# Sheet1.net
KiCad netlist of a schematic drawn in Altium Designer
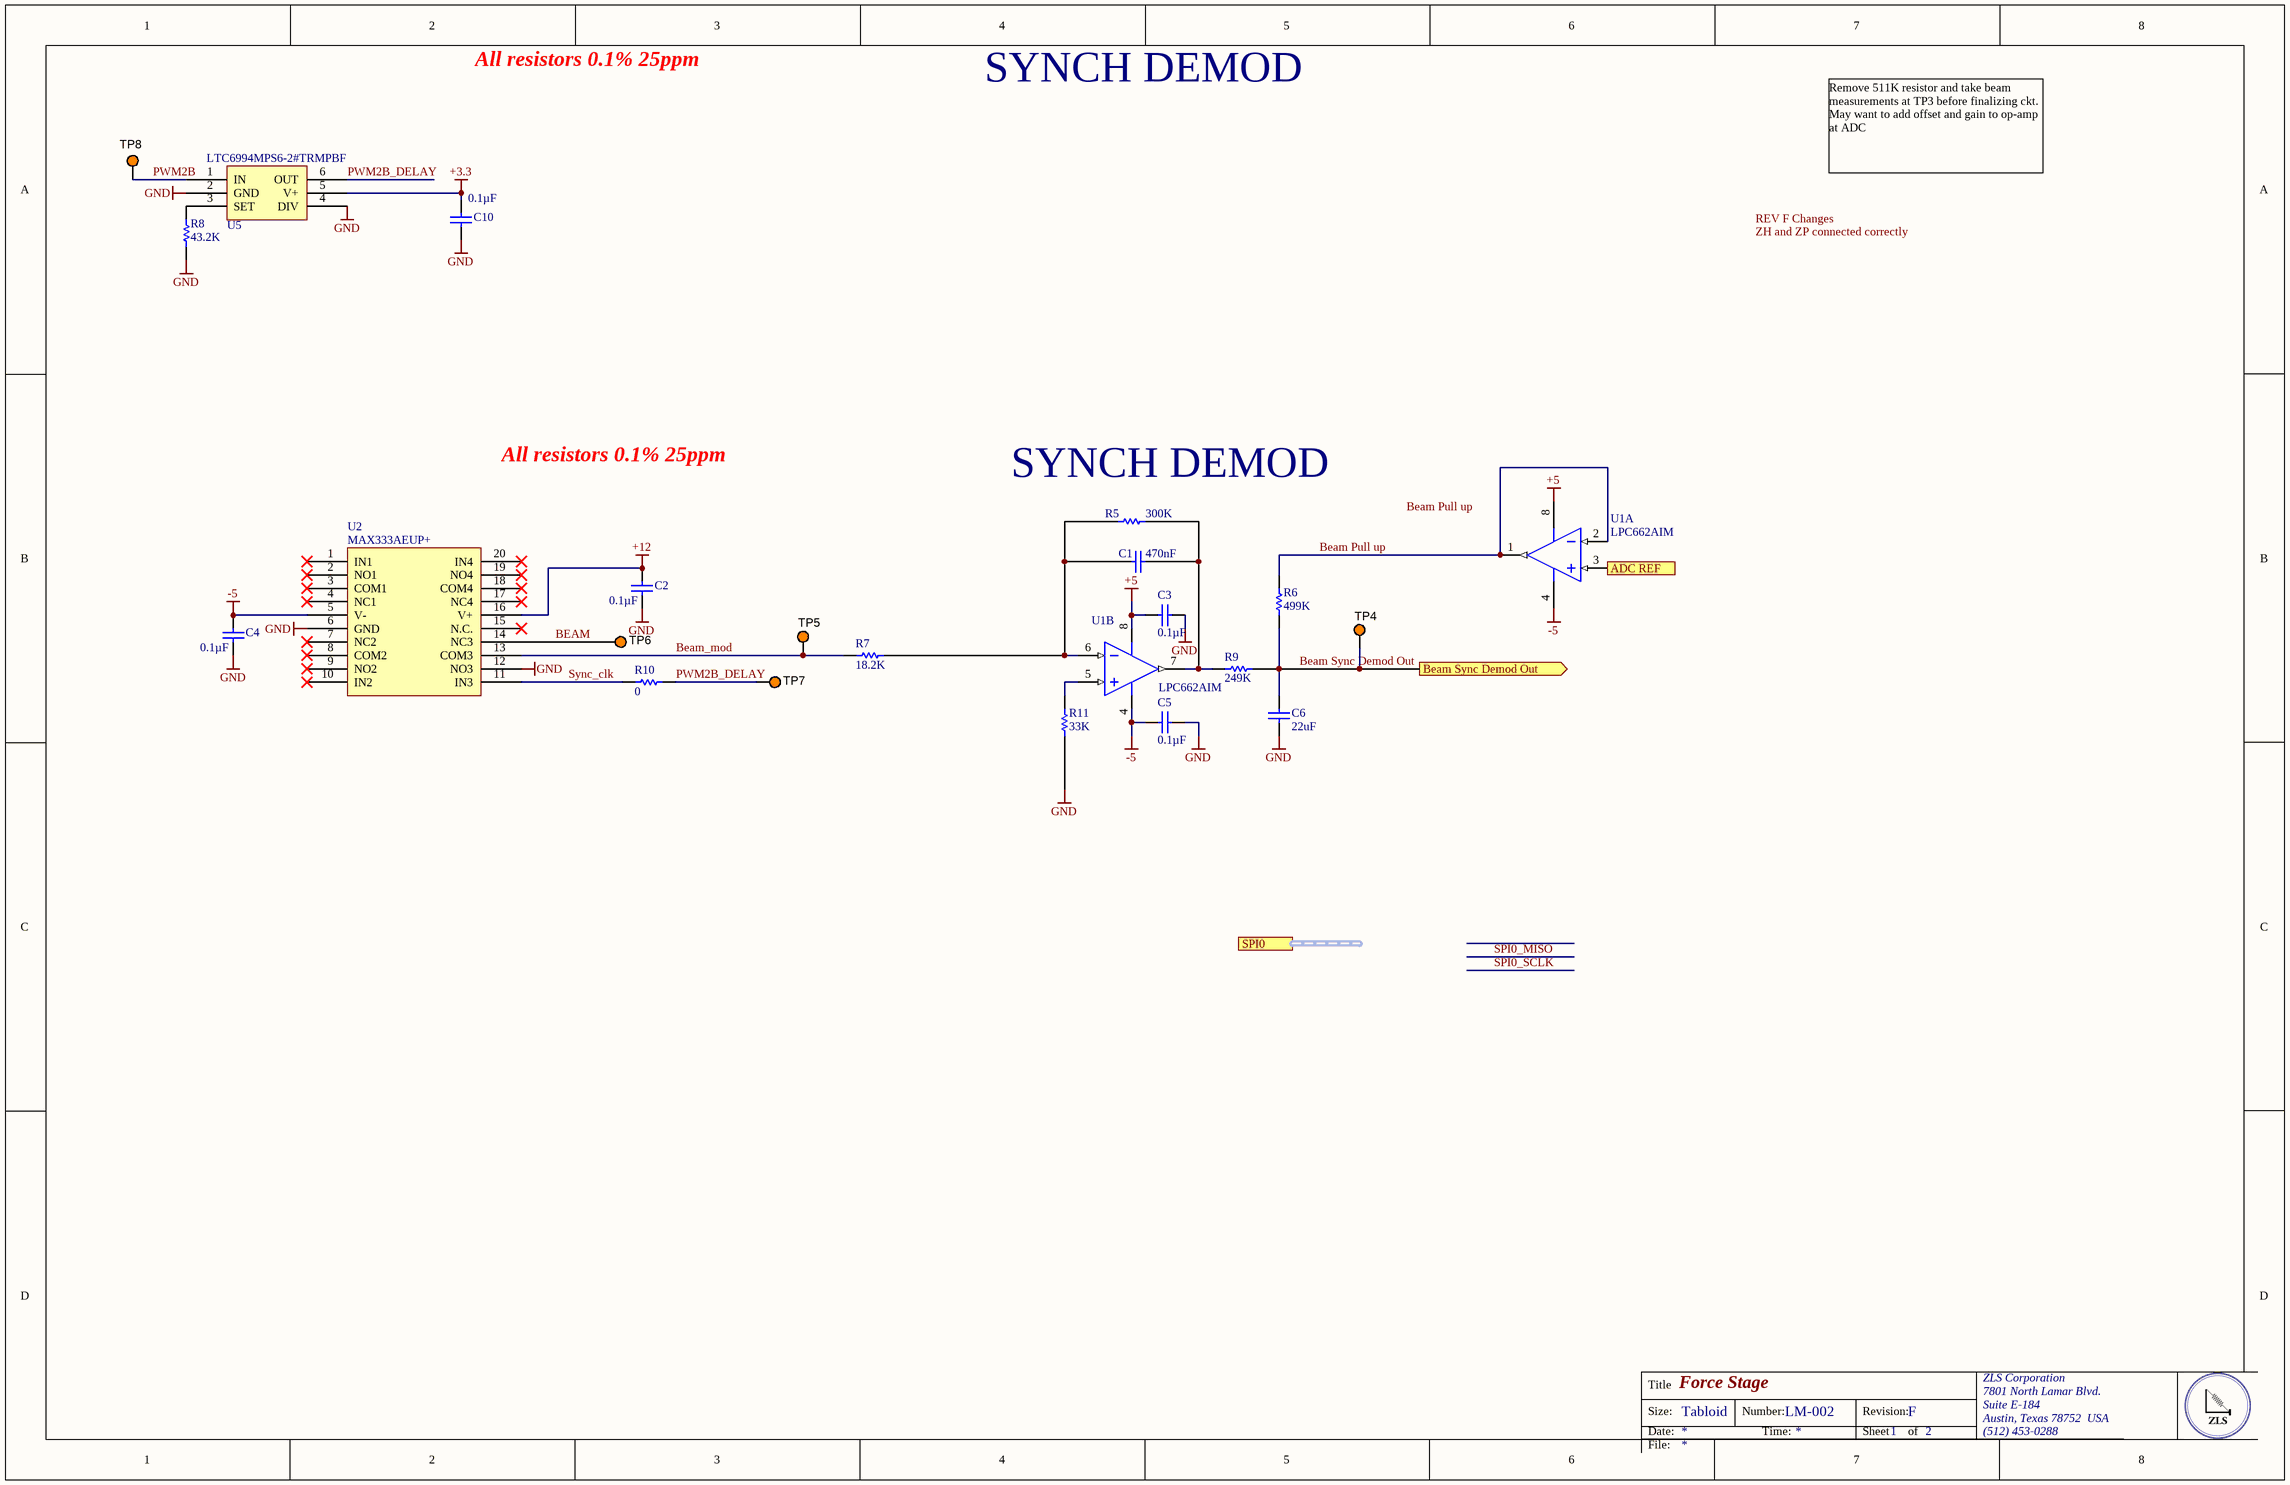
[diagram p0: Sheet1.SchDoc]

(export (version "E")
  (design (tool "Eeschema 10.0.6"))
  (components
    (comp (ref "C1")
      (value "470nF")
      (footprint "CAPC0805(2012)75_L")
      (description "CAP CER 0.47UF 25V X7R 0805")
      (fields
        (field (name "MANUFACTURER") "Murata Electronics North America")
        (field (name "MANUFACTURER PART NUMBER") "GRM219R71E474KA88D")
      )
      (libsource (lib "Altium Content Vault") (part "CMP-1036-02117-1"))
    )
    (comp (ref "C2")
      (value "CAP CER 0.1UF 25V X7R 0805")
      (footprint "CAPC0805(2012)145_N")
      (fields
        (field (name "MANUFACTURER") "Murata Electronics North America")
        (field (name "MANUFACTURER PART NUMBER") "GRM21BR71E104KA01L")
        (field (name "CAPACITANCE") "0.1µF")
        (field (name "TOLERANCE") "±10%")
      )
      (libsource (lib "Altium Content Vault") (part "CMP-1036-04795-1"))
    )
    (comp (ref "C3")
      (value "CAP CER 0.1UF 25V X7R 0805")
      (footprint "CAPC0805(2012)145_N")
      (fields
        (field (name "MANUFACTURER") "Murata Electronics North America")
        (field (name "MANUFACTURER PART NUMBER") "GRM21BR71E104KA01L")
        (field (name "CAPACITANCE") "0.1µF")
        (field (name "TOLERANCE") "±10%")
      )
      (libsource (lib "Altium Content Vault") (part "CMP-1036-04795-1"))
    )
    (comp (ref "C4")
      (value "CAP CER 0.1UF 25V X7R 0805")
      (footprint "CAPC0805(2012)145_N")
      (fields
        (field (name "MANUFACTURER") "Murata Electronics North America")
        (field (name "MANUFACTURER PART NUMBER") "GRM21BR71E104KA01L")
        (field (name "CAPACITANCE") "0.1µF")
        (field (name "TOLERANCE") "±10%")
      )
      (libsource (lib "Altium Content Vault") (part "CMP-1036-04795-1"))
    )
    (comp (ref "C5")
      (value "CAP CER 0.1UF 25V X7R 0805")
      (footprint "CAPC0805(2012)145_N")
      (fields
        (field (name "MANUFACTURER") "Murata Electronics North America")
        (field (name "MANUFACTURER PART NUMBER") "GRM21BR71E104KA01L")
        (field (name "CAPACITANCE") "0.1µF")
        (field (name "TOLERANCE") "±10%")
      )
      (libsource (lib "Altium Content Vault") (part "CMP-1036-04795-1"))
    )
    (comp (ref "C6")
      (value "22uF")
      (footprint "CAPC0805(2012)75_L")
      (description "CAP CER 22UF 25V X5R 0805")
      (fields
        (field (name "MANUFACTURER") "Murata Electronics North America")
        (field (name "MANUFACTURER PART NUMBER") "GRM21BR61E226ME44L")
      )
      (libsource (lib "Altium Content Vault") (part "CMP-1036-02117-1"))
    )
    (comp (ref "C10")
      (value "CAP CER 0.1UF 25V X7R 0805")
      (footprint "CAPC0805(2012)145_N")
      (fields
        (field (name "MANUFACTURER") "Murata Electronics North America")
        (field (name "MANUFACTURER PART NUMBER") "GRM21BR71E104KA01L")
        (field (name "CAPACITANCE") "0.1µF")
        (field (name "TOLERANCE") "±10%")
      )
      (libsource (lib "Altium Content Vault") (part "CMP-1036-04795-1"))
    )
    (comp (ref "R5")
      (value "300K")
      (footprint "RESC0805(2012)_L")
      (description "RES SMD 300K OHM 1% 1/8W 0805")
      (fields
        (field (name "MANUFACTURER") "Vishay Dale")
        (field (name "MANUFACTURER PART NUMBER") "CRCW0805300KFKEAHP")
      )
      (libsource (lib "Altium Content Vault") (part "CMP-1013-00215-1"))
    )
    (comp (ref "R6")
      (value "499K")
      (footprint "RESC0805(2012)_L")
      (description "RES SMD 499K OHM 0.1% 1/8W 0805")
      (fields
        (field (name "MANUFACTURER") "Panasonic Electronic Components")
        (field (name "MANUFACTURER PART NUMBER") "ERA-6AEB4993V")
      )
      (libsource (lib "Altium Content Vault") (part "CMP-1013-00215-1"))
    )
    (comp (ref "R7")
      (value "18.2K")
      (footprint "RESC0805(2012)_L")
      (description "RES SMD 18.2K OHM 1% 1/8W 0805")
      (fields
        (field (name "MANUFACTURER") "Panasonic Electronic Components")
        (field (name "MANUFACTURER PART NUMBER") "ERJ-6ENF1822V")
      )
      (libsource (lib "Altium Content Vault") (part "CMP-1013-00215-1"))
    )
    (comp (ref "R8")
      (value "43.2K")
      (footprint "RESC0805(2012)_L")
      (description "RES SMD 43.2K OHM 1% 1/8W 0805")
      (fields
        (field (name "MANUFACTURER") "Vishay Dale")
        (field (name "MANUFACTURER PART NUMBER") "CRCW080543K2FKEA")
      )
      (libsource (lib "Altium Content Vault") (part "CMP-1013-00215-1"))
    )
    (comp (ref "R9")
      (value "249K")
      (footprint "RESC0805(2012)_L")
      (description "RES SMD 249K OHM 0.1% 1/8W 0805")
      (fields
        (field (name "MANUFACTURER") "Panasonic Electronic Components")
        (field (name "MANUFACTURER PART NUMBER") "ERA-6AEB2493V")
      )
      (libsource (lib "Altium Content Vault") (part "CMP-1013-00215-1"))
    )
    (comp (ref "R10")
      (value "0")
      (footprint "RESC0805(2012)_L")
      (description "RES SMD 0 OHM JUMPER 1/8W 0805")
      (fields
        (field (name "MANUFACTURER") "Panasonic Electronic Components")
        (field (name "MANUFACTURER PART NUMBER") "ERJ-6GEY0R00V")
      )
      (libsource (lib "Altium Content Vault") (part "CMP-1013-00215-1"))
    )
    (comp (ref "R11")
      (value "33K")
      (footprint "RESC0805(2012)_L")
      (description "RES SMD 33K OHM 1% 1/2W 0805")
      (fields
        (field (name "MANUFACTURER") "Vishay Dale")
        (field (name "MANUFACTURER PART NUMBER") "CRCW080533K0FKEAHP")
      )
      (libsource (lib "Altium Content Vault") (part "CMP-1013-00215-1"))
    )
    (comp (ref "TP4")
      (value "5003")
      (footprint "KSTN-5003")
      (description "Test Point, Orange, 1-Pin THD, RoHS")
      (libsource (lib "Altium Content Vault") (part "CMP-1672-00009-1"))
    )
    (comp (ref "TP5")
      (value "5003")
      (footprint "KSTN-5003")
      (description "Test Point, Orange, 1-Pin THD, RoHS")
      (libsource (lib "Altium Content Vault") (part "CMP-1672-00009-1"))
    )
    (comp (ref "TP6")
      (value "5003")
      (footprint "KSTN-5003")
      (description "Test Point, Orange, 1-Pin THD, RoHS")
      (libsource (lib "Altium Content Vault") (part "CMP-1672-00009-1"))
    )
    (comp (ref "TP7")
      (value "5003")
      (footprint "KSTN-5003")
      (description "Test Point, Orange, 1-Pin THD, RoHS")
      (libsource (lib "Altium Content Vault") (part "CMP-1672-00009-1"))
    )
    (comp (ref "TP8")
      (value "5003")
      (footprint "KSTN-5003")
      (description "Test Point, Orange, 1-Pin THD, RoHS")
      (libsource (lib "Altium Content Vault") (part "CMP-1672-00009-1"))
    )
    (comp (ref "U1")
      (value "LPC662AIM")
      (footprint "D0008A_M")
      (description "Low Power CMOS Dual Operational Amplifier, 8-pin Narrow SOIC")
      (fields
        (field (name "MANUFACTURER") "Texas Instruments")
        (field (name "MANUFACTURER PART NUMBER") "LPC662AIM/NOPB")
      )
      (libsource (lib "Altium Content Vault") (part "CMP-0055-00867-3"))
    )
    (comp (ref "U2")
      (value "MAX333AEUP+")
      (footprint "TSOP65P640X90-20N")
      (description "IC SWITCH QUAD SPDT 20TSSOP")
      (fields (field (name "MANUFACTURER") "Maxim Integrated") (field (name "BASE PART NUMBER") "MAX333"))
      (libsource (lib "ZLS_Schematic_lib") (part "MAX333CWP+"))
    )
    (comp (ref "U5")
      (value "LTC6994MPS6-2#TRMPBF")
      (footprint "LTC6994MPS6-2#TRMPBF")
      (description "IC DELAY BLOCK 8TAP PROG TSOT23")
      (fields
        (field (name "MANUFACTURER") "Linear Technology/Analog Devices")
        (field (name "MANUFACTURER PART NUMBER") "LTC6994CS6-2#TRMPBF")
      )
      (libsource (lib "ZLS_Schematic_lib") (part "LTC6994MPS6-2#TRMPBF"))
    )
  )
  (nets
    (net (code "2") (name "+3.3") (class "Default")
      (node (ref "C10") (pin "1") (pinfunction "1_1") (pintype "passive"))
      (node (ref "U5") (pin "5") (pinfunction "V+_5") (pintype "passive"))
    )
    (net (code "3") (name "+5") (class "Default")
      (node (ref "C3") (pin "1") (pinfunction "1_1") (pintype "passive"))
      (node (ref "U1") (pin "8") (pinfunction "V+_8") (pintype "power_in"))
    )
    (net (code "4") (name "+12") (class "Default")
      (node (ref "C2") (pin "1") (pinfunction "1_1") (pintype "passive"))
      (node (ref "U2") (pin "16") (pinfunction "V+_16") (pintype "power_in"))
    )
    (net (code "5") (name "-5") (class "Default")
      (node (ref "C4") (pin "1") (pinfunction "1_1") (pintype "passive"))
      (node (ref "C5") (pin "1") (pinfunction "1_1") (pintype "passive"))
      (node (ref "U1") (pin "4") (pinfunction "V-_4") (pintype "power_in"))
      (node (ref "U2") (pin "5") (pinfunction "V-_5") (pintype "power_in"))
    )
    (net (code "6") (name "/ADC REF") (class "Default")
      (node (ref "U1") (pin "3") (pinfunction "INA+_3") (pintype "input"))
    )
    (net (code "7") (name "/BEAM") (class "Default")
      (node (ref "TP6") (pin "1") (pinfunction "1_1") (pintype "passive"))
      (node (ref "U2") (pin "14") (pinfunction "NC3_14") (pintype "passive"))
    )
    (net (code "8") (name "/Beam Pull up") (class "Default")
      (node (ref "R6") (pin "2") (pinfunction "2_2") (pintype "passive"))
      (node (ref "U1") (pin "1") (pinfunction "OUTA_1") (pintype "output"))
      (node (ref "U1") (pin "2") (pinfunction "INA-_2") (pintype "input"))
    )
    (net (code "9") (name "/Beam Sync Demod Out") (class "Default")
      (node (ref "C6") (pin "2") (pinfunction "2_2") (pintype "passive"))
      (node (ref "R6") (pin "1") (pinfunction "1_1") (pintype "passive"))
      (node (ref "R9") (pin "1") (pinfunction "1_1") (pintype "passive"))
      (node (ref "TP4") (pin "1") (pinfunction "1_1") (pintype "passive"))
    )
    (net (code "10") (name "/Beam_mod") (class "Default")
      (node (ref "R7") (pin "2") (pinfunction "2_2") (pintype "passive"))
      (node (ref "TP5") (pin "1") (pinfunction "1_1") (pintype "passive"))
      (node (ref "U2") (pin "13") (pinfunction "COM3_13") (pintype "passive"))
    )
    (net (code "11") (name "/PWM2B") (class "Default")
      (node (ref "TP8") (pin "1") (pinfunction "1_1") (pintype "passive"))
      (node (ref "U5") (pin "1") (pinfunction "IN_1") (pintype "passive"))
    )
    (net (code "12") (name "/PWM2B_DELAY") (class "Default")
      (node (ref "R10") (pin "1") (pinfunction "1_1") (pintype "passive"))
      (node (ref "TP7") (pin "1") (pinfunction "1_1") (pintype "passive"))
      (node (ref "U5") (pin "6") (pinfunction "OUT_6") (pintype "passive"))
    )
    (net (code "17") (name "/Sync_clk") (class "Default")
      (node (ref "R10") (pin "2") (pinfunction "2_2") (pintype "passive"))
      (node (ref "U2") (pin "11") (pinfunction "IN3_11") (pintype "passive"))
    )
    (net (code "19") (name "GND") (class "Default")
      (node (ref "C10") (pin "2") (pinfunction "2_2") (pintype "passive"))
      (node (ref "C2") (pin "2") (pinfunction "2_2") (pintype "passive"))
      (node (ref "C3") (pin "2") (pinfunction "2_2") (pintype "passive"))
      (node (ref "C4") (pin "2") (pinfunction "2_2") (pintype "passive"))
      (node (ref "C5") (pin "2") (pinfunction "2_2") (pintype "passive"))
      (node (ref "C6") (pin "1") (pinfunction "1_1") (pintype "passive"))
      (node (ref "R11") (pin "1") (pinfunction "1_1") (pintype "passive"))
      (node (ref "R8") (pin "2") (pinfunction "2_2") (pintype "passive"))
      (node (ref "U2") (pin "12") (pinfunction "NO3_12") (pintype "passive"))
      (node (ref "U2") (pin "6") (pinfunction "GND_6") (pintype "passive"))
      (node (ref "U5") (pin "2") (pinfunction "GND_2") (pintype "passive"))
      (node (ref "U5") (pin "4") (pinfunction "DIV_4") (pintype "passive"))
    )
    (net (code "20") (name "Net-(U1B-INB+)") (class "Default")
      (node (ref "R11") (pin "2") (pinfunction "2_2") (pintype "passive"))
      (node (ref "U1") (pin "5") (pinfunction "INB+_5") (pintype "input"))
    )
    (net (code "21") (name "Net-(U1B-INB-)") (class "Default")
      (node (ref "C1") (pin "1") (pinfunction "1_1") (pintype "passive"))
      (node (ref "R5") (pin "2") (pinfunction "2_2") (pintype "passive"))
      (node (ref "R7") (pin "1") (pinfunction "1_1") (pintype "passive"))
      (node (ref "U1") (pin "6") (pinfunction "INB-_6") (pintype "input"))
    )
    (net (code "22") (name "Net-(U1B-OUTB)") (class "Default")
      (node (ref "C1") (pin "2") (pinfunction "2_2") (pintype "passive"))
      (node (ref "R5") (pin "1") (pinfunction "1_1") (pintype "passive"))
      (node (ref "R9") (pin "2") (pinfunction "2_2") (pintype "passive"))
      (node (ref "U1") (pin "7") (pinfunction "OUTB_7") (pintype "output"))
    )
    (net (code "23") (name "Net-(U5-SET)") (class "Default")
      (node (ref "R8") (pin "1") (pinfunction "1_1") (pintype "passive"))
      (node (ref "U5") (pin "3") (pinfunction "SET_3") (pintype "passive"))
    )
    (net (code "24") (name "unconnected-(U2-COM1-Pad3)") (class "Default")
      (node (ref "U2") (pin "3") (pinfunction "COM1_3") (pintype "passive+no_connect"))
    )
    (net (code "25") (name "unconnected-(U2-COM2-Pad8)") (class "Default")
      (node (ref "U2") (pin "8") (pinfunction "COM2_8") (pintype "passive+no_connect"))
    )
    (net (code "26") (name "unconnected-(U2-COM4-Pad18)") (class "Default")
      (node (ref "U2") (pin "18") (pinfunction "COM4_18") (pintype "passive+no_connect"))
    )
    (net (code "27") (name "unconnected-(U2-IN1-Pad1)") (class "Default")
      (node (ref "U2") (pin "1") (pinfunction "IN1_1") (pintype "passive+no_connect"))
    )
    (net (code "28") (name "unconnected-(U2-IN2-Pad10)") (class "Default")
      (node (ref "U2") (pin "10") (pinfunction "IN2_10") (pintype "passive+no_connect"))
    )
    (net (code "29") (name "unconnected-(U2-IN4-Pad20)") (class "Default")
      (node (ref "U2") (pin "20") (pinfunction "IN4_20") (pintype "passive+no_connect"))
    )
    (net (code "30") (name "unconnected-(U2-N.C.-Pad15)") (class "Default")
      (node (ref "U2") (pin "15") (pinfunction "N.C._15") (pintype "passive+no_connect"))
    )
    (net (code "31") (name "unconnected-(U2-NC1-Pad4)") (class "Default")
      (node (ref "U2") (pin "4") (pinfunction "NC1_4") (pintype "passive+no_connect"))
    )
    (net (code "32") (name "unconnected-(U2-NC2-Pad7)") (class "Default")
      (node (ref "U2") (pin "7") (pinfunction "NC2_7") (pintype "passive+no_connect"))
    )
    (net (code "33") (name "unconnected-(U2-NC4-Pad17)") (class "Default")
      (node (ref "U2") (pin "17") (pinfunction "NC4_17") (pintype "passive+no_connect"))
    )
    (net (code "34") (name "unconnected-(U2-NO1-Pad2)") (class "Default")
      (node (ref "U2") (pin "2") (pinfunction "NO1_2") (pintype "passive+no_connect"))
    )
    (net (code "35") (name "unconnected-(U2-NO2-Pad9)") (class "Default")
      (node (ref "U2") (pin "9") (pinfunction "NO2_9") (pintype "passive+no_connect"))
    )
    (net (code "36") (name "unconnected-(U2-NO4-Pad19)") (class "Default")
      (node (ref "U2") (pin "19") (pinfunction "NO4_19") (pintype "passive+no_connect"))
    )
  )
)
